# femto.net
KiCad netlist of a schematic drawn in EAGLE
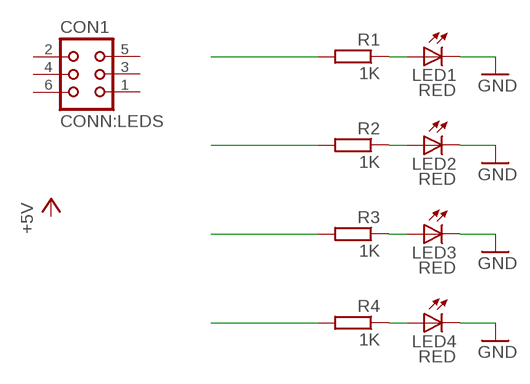
[diagram p0: schematic, sheet 1]

(export (version "E")
  (design (tool "Eeschema 10.0.6"))
  (components
    (comp (ref "CON1")
      (value "CONN:LEDS")
      (footprint "eagle-import:IDC-2_3")
      (libsource (lib "eagle-import") (part "CONN{colon}LEDS"))
    )
    (comp (ref "LED1")
      (value "RED")
      (footprint "eagle-import:CHIP-LED0805")
      (libsource (lib "eagle-import") (part "LEDCHIP-LED0805"))
    )
    (comp (ref "LED2")
      (value "RED")
      (footprint "eagle-import:CHIP-LED0805")
      (libsource (lib "eagle-import") (part "LEDCHIP-LED0805"))
    )
    (comp (ref "LED3")
      (value "RED")
      (footprint "eagle-import:CHIP-LED0805")
      (libsource (lib "eagle-import") (part "LEDCHIP-LED0805"))
    )
    (comp (ref "LED4")
      (value "RED")
      (footprint "eagle-import:CHIP-LED0805")
      (libsource (lib "eagle-import") (part "LEDCHIP-LED0805"))
    )
    (comp (ref "R1")
      (value "1K")
      (footprint "eagle-import:R0805")
      (libsource (lib "eagle-import") (part "R-EU_R0805"))
    )
    (comp (ref "R2")
      (value "1K")
      (footprint "eagle-import:R0805")
      (libsource (lib "eagle-import") (part "R-EU_R0805"))
    )
    (comp (ref "R3")
      (value "1K")
      (footprint "eagle-import:R0805")
      (libsource (lib "eagle-import") (part "R-EU_R0805"))
    )
    (comp (ref "R4")
      (value "1K")
      (footprint "eagle-import:R0805")
      (libsource (lib "eagle-import") (part "R-EU_R0805"))
    )
  )
  (nets
    (net (code "2") (name "GND") (class "Default")
      (node (ref "LED1") (pin "C") (pinfunction "C_C") (pintype "passive"))
      (node (ref "LED2") (pin "C") (pinfunction "C_C") (pintype "passive"))
      (node (ref "LED3") (pin "C") (pinfunction "C_C") (pintype "passive"))
      (node (ref "LED4") (pin "C") (pinfunction "C_C") (pintype "passive"))
    )
    (net (code "3") (name "Net-(LED1-PadA)") (class "Default")
      (node (ref "LED1") (pin "A") (pinfunction "A_A") (pintype "passive"))
      (node (ref "R1") (pin "1") (pinfunction "1_1") (pintype "passive"))
    )
    (net (code "4") (name "Net-(LED2-PadA)") (class "Default")
      (node (ref "LED2") (pin "A") (pinfunction "A_A") (pintype "passive"))
      (node (ref "R2") (pin "1") (pinfunction "1_1") (pintype "passive"))
    )
    (net (code "5") (name "Net-(LED3-PadA)") (class "Default")
      (node (ref "LED3") (pin "A") (pinfunction "A_A") (pintype "passive"))
      (node (ref "R3") (pin "1") (pinfunction "1_1") (pintype "passive"))
    )
    (net (code "6") (name "Net-(LED4-PadA)") (class "Default")
      (node (ref "LED4") (pin "A") (pinfunction "A_A") (pintype "passive"))
      (node (ref "R4") (pin "1") (pinfunction "1_1") (pintype "passive"))
    )
    (net (code "7") (name "unconnected-(CON1-BLUE-Pad6)") (class "Default")
      (node (ref "CON1") (pin "6") (pinfunction "BLUE_6") (pintype "passive"))
    )
    (net (code "8") (name "unconnected-(CON1-GND-Pad1)") (class "Default")
      (node (ref "CON1") (pin "1") (pinfunction "GND_1") (pintype "passive"))
    )
    (net (code "9") (name "unconnected-(CON1-GREEN-Pad4)") (class "Default")
      (node (ref "CON1") (pin "4") (pinfunction "GREEN_4") (pintype "passive"))
    )
    (net (code "10") (name "unconnected-(CON1-RED-Pad2)") (class "Default")
      (node (ref "CON1") (pin "2") (pinfunction "RED_2") (pintype "passive"))
    )
    (net (code "11") (name "unconnected-(CON1-UV-Pad3)") (class "Default")
      (node (ref "CON1") (pin "3") (pinfunction "UV_3") (pintype "passive"))
    )
    (net (code "12") (name "unconnected-(CON1-WHITE-Pad5)") (class "Default")
      (node (ref "CON1") (pin "5") (pinfunction "WHITE_5") (pintype "passive"))
    )
    (net (code "13") (name "unconnected-(R1-Pad2)") (class "Default")
      (node (ref "R1") (pin "2") (pinfunction "2_2") (pintype "passive"))
    )
    (net (code "14") (name "unconnected-(R2-Pad2)") (class "Default")
      (node (ref "R2") (pin "2") (pinfunction "2_2") (pintype "passive"))
    )
    (net (code "15") (name "unconnected-(R3-Pad2)") (class "Default")
      (node (ref "R3") (pin "2") (pinfunction "2_2") (pintype "passive"))
    )
    (net (code "16") (name "unconnected-(R4-Pad2)") (class "Default")
      (node (ref "R4") (pin "2") (pinfunction "2_2") (pintype "passive"))
    )
  )
)
